# SHIELD5.net
KiCad netlist of a schematic drawn in Altium Designer
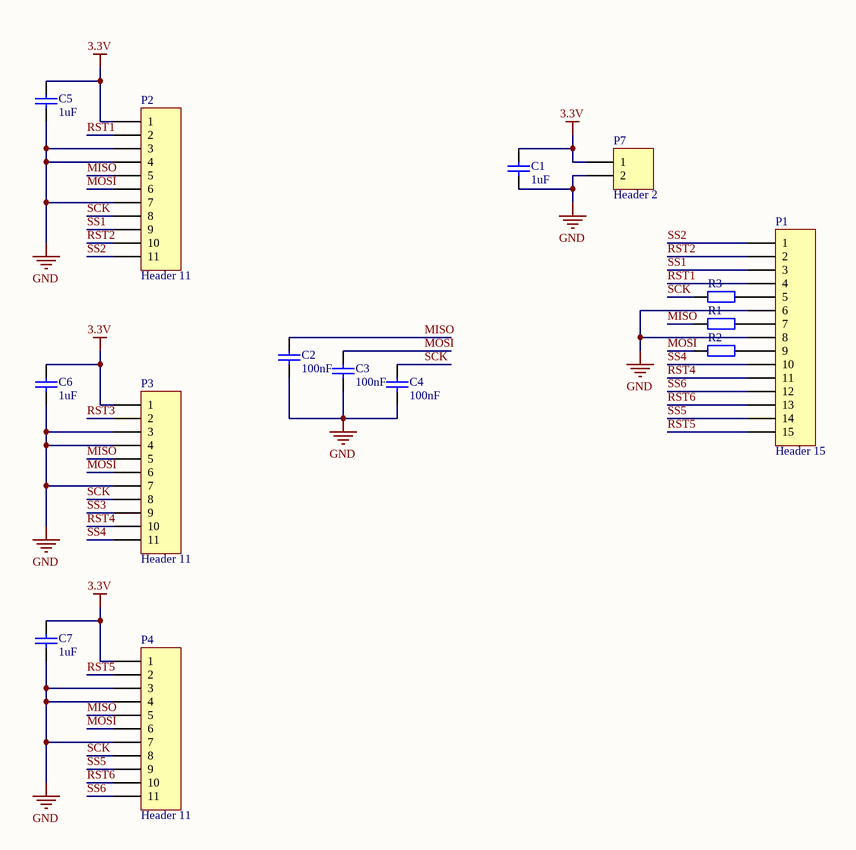
[diagram p0: SHIELD5.SchDoc]

(export (version "E")
  (design (tool "Eeschema 10.0.6"))
  (components
    (comp (ref "C1")
      (value "1uF")
      (footprint "C0805")
      (description "Capacitor")
      (fields (field (name "Comment") "Cap") (field (name "PUBLISHER") "Altium Limited"))
      (libsource (lib "Library") (part "Cap"))
    )
    (comp (ref "C2")
      (value "100nF")
      (footprint "C0805")
      (description "Capacitor")
      (fields (field (name "Comment") "Cap") (field (name "PUBLISHER") "Altium Limited"))
      (libsource (lib "Library") (part "Cap"))
    )
    (comp (ref "C3")
      (value "100nF")
      (footprint "C0805")
      (description "Capacitor")
      (fields (field (name "Comment") "Cap") (field (name "PUBLISHER") "Altium Limited"))
      (libsource (lib "Library") (part "Cap"))
    )
    (comp (ref "C4")
      (value "100nF")
      (footprint "C0805")
      (description "Capacitor")
      (fields (field (name "Comment") "Cap") (field (name "PUBLISHER") "Altium Limited"))
      (libsource (lib "Library") (part "Cap"))
    )
    (comp (ref "C5")
      (value "1uF")
      (footprint "C0805")
      (description "Capacitor")
      (fields (field (name "Comment") "Cap") (field (name "PUBLISHER") "Altium Limited"))
      (libsource (lib "Library") (part "Cap"))
    )
    (comp (ref "C6")
      (value "1uF")
      (footprint "C0805")
      (description "Capacitor")
      (fields (field (name "Comment") "Cap") (field (name "PUBLISHER") "Altium Limited"))
      (libsource (lib "Library") (part "Cap"))
    )
    (comp (ref "C7")
      (value "1uF")
      (footprint "C0805")
      (description "Capacitor")
      (fields (field (name "Comment") "Cap") (field (name "PUBLISHER") "Altium Limited"))
      (libsource (lib "Library") (part "Cap"))
    )
    (comp (ref "P1")
      (value "Header 15")
      (footprint "HDR1X15")
      (description "Header, 15-Pin")
      (fields (field (name "PUBLISHER") "Altium Limited"))
      (libsource (lib "Miscellaneous Connectors") (part "Header 15"))
    )
    (comp (ref "P2")
      (value "Header 11")
      (footprint "HDR1X11")
      (description "Header, 11-Pin")
      (fields (field (name "PUBLISHER") "Altium Limited"))
      (libsource (lib "Miscellaneous Connectors") (part "Header 11"))
    )
    (comp (ref "P3")
      (value "Header 11")
      (footprint "HDR1X11")
      (description "Header, 11-Pin")
      (fields (field (name "PUBLISHER") "Altium Limited"))
      (libsource (lib "Miscellaneous Connectors") (part "Header 11"))
    )
    (comp (ref "P4")
      (value "Header 11")
      (footprint "HDR1X11")
      (description "Header, 11-Pin")
      (fields (field (name "PUBLISHER") "Altium Limited"))
      (libsource (lib "Miscellaneous Connectors") (part "Header 11"))
    )
    (comp (ref "P7")
      (value "Header 2")
      (footprint "HDR1X2")
      (description "Header, 2-Pin")
      (fields (field (name "PUBLISHER") "Altium Limited"))
      (libsource (lib "Miscellaneous Connectors") (part "Header 2"))
    )
    (comp (ref "R1")
      (value "Res2")
      (footprint "6-0805_N")
      (description "Resistor")
      (fields (field (name "PUBLISHER") "Altium Limited"))
      (libsource (lib "Library") (part "Res2"))
    )
    (comp (ref "R2")
      (value "Res2")
      (footprint "6-0805_N")
      (description "Resistor")
      (fields (field (name "PUBLISHER") "Altium Limited"))
      (libsource (lib "Library") (part "Res2"))
    )
    (comp (ref "R3")
      (value "Res2")
      (footprint "6-0805_N")
      (description "Resistor")
      (fields (field (name "PUBLISHER") "Altium Limited"))
      (libsource (lib "Library") (part "Res2"))
    )
  )
  (nets
    (net (code "1") (name "/MISO") (class "Default")
      (node (ref "C2") (pin "2") (pinfunction "2_2") (pintype "passive"))
      (node (ref "P2") (pin "5") (pinfunction "5_5") (pintype "passive"))
      (node (ref "P3") (pin "5") (pinfunction "5_5") (pintype "passive"))
      (node (ref "P4") (pin "5") (pinfunction "5_5") (pintype "passive"))
      (node (ref "R1") (pin "1") (pinfunction "1_1") (pintype "passive"))
    )
    (net (code "2") (name "/MOSI") (class "Default")
      (node (ref "C3") (pin "1") (pinfunction "1_1") (pintype "passive"))
      (node (ref "P2") (pin "6") (pinfunction "6_6") (pintype "passive"))
      (node (ref "P3") (pin "6") (pinfunction "6_6") (pintype "passive"))
      (node (ref "P4") (pin "6") (pinfunction "6_6") (pintype "passive"))
      (node (ref "R2") (pin "1") (pinfunction "1_1") (pintype "passive"))
    )
    (net (code "3") (name "/RST1") (class "Default")
      (node (ref "P1") (pin "4") (pinfunction "4_4") (pintype "passive"))
      (node (ref "P2") (pin "2") (pinfunction "2_2") (pintype "passive"))
    )
    (net (code "4") (name "/RST2") (class "Default")
      (node (ref "P1") (pin "2") (pinfunction "2_2") (pintype "passive"))
      (node (ref "P2") (pin "10") (pinfunction "10_10") (pintype "passive"))
    )
    (net (code "5") (name "/RST3") (class "Default")
      (node (ref "P3") (pin "2") (pinfunction "2_2") (pintype "passive"))
    )
    (net (code "6") (name "/RST4") (class "Default")
      (node (ref "P1") (pin "11") (pinfunction "11_11") (pintype "passive"))
      (node (ref "P3") (pin "10") (pinfunction "10_10") (pintype "passive"))
    )
    (net (code "7") (name "/RST5") (class "Default")
      (node (ref "P1") (pin "15") (pinfunction "15_15") (pintype "passive"))
      (node (ref "P4") (pin "2") (pinfunction "2_2") (pintype "passive"))
    )
    (net (code "8") (name "/RST6") (class "Default")
      (node (ref "P1") (pin "13") (pinfunction "13_13") (pintype "passive"))
      (node (ref "P4") (pin "10") (pinfunction "10_10") (pintype "passive"))
    )
    (net (code "9") (name "/SCK") (class "Default")
      (node (ref "C4") (pin "1") (pinfunction "1_1") (pintype "passive"))
      (node (ref "P2") (pin "8") (pinfunction "8_8") (pintype "passive"))
      (node (ref "P3") (pin "8") (pinfunction "8_8") (pintype "passive"))
      (node (ref "P4") (pin "8") (pinfunction "8_8") (pintype "passive"))
      (node (ref "R3") (pin "1") (pinfunction "1_1") (pintype "passive"))
    )
    (net (code "10") (name "/SS1") (class "Default")
      (node (ref "P1") (pin "3") (pinfunction "3_3") (pintype "passive"))
      (node (ref "P2") (pin "9") (pinfunction "9_9") (pintype "passive"))
    )
    (net (code "11") (name "/SS2") (class "Default")
      (node (ref "P1") (pin "1") (pinfunction "1_1") (pintype "passive"))
      (node (ref "P2") (pin "11") (pinfunction "11_11") (pintype "passive"))
    )
    (net (code "12") (name "/SS3") (class "Default")
      (node (ref "P3") (pin "9") (pinfunction "9_9") (pintype "passive"))
    )
    (net (code "13") (name "/SS4") (class "Default")
      (node (ref "P1") (pin "10") (pinfunction "10_10") (pintype "passive"))
      (node (ref "P3") (pin "11") (pinfunction "11_11") (pintype "passive"))
    )
    (net (code "14") (name "/SS5") (class "Default")
      (node (ref "P1") (pin "14") (pinfunction "14_14") (pintype "passive"))
      (node (ref "P4") (pin "9") (pinfunction "9_9") (pintype "passive"))
    )
    (net (code "15") (name "/SS6") (class "Default")
      (node (ref "P1") (pin "12") (pinfunction "12_12") (pintype "passive"))
      (node (ref "P4") (pin "11") (pinfunction "11_11") (pintype "passive"))
    )
    (net (code "16") (name "3.3V") (class "Default")
      (node (ref "C1") (pin "2") (pinfunction "2_2") (pintype "passive"))
      (node (ref "C5") (pin "2") (pinfunction "2_2") (pintype "passive"))
      (node (ref "C6") (pin "2") (pinfunction "2_2") (pintype "passive"))
      (node (ref "C7") (pin "2") (pinfunction "2_2") (pintype "passive"))
      (node (ref "P2") (pin "1") (pinfunction "1_1") (pintype "passive"))
      (node (ref "P3") (pin "1") (pinfunction "1_1") (pintype "passive"))
      (node (ref "P4") (pin "1") (pinfunction "1_1") (pintype "passive"))
      (node (ref "P7") (pin "1") (pinfunction "1_1") (pintype "passive"))
    )
    (net (code "17") (name "GND") (class "Default")
      (node (ref "C1") (pin "1") (pinfunction "1_1") (pintype "passive"))
      (node (ref "C2") (pin "1") (pinfunction "1_1") (pintype "passive"))
      (node (ref "C3") (pin "2") (pinfunction "2_2") (pintype "passive"))
      (node (ref "C4") (pin "2") (pinfunction "2_2") (pintype "passive"))
      (node (ref "C5") (pin "1") (pinfunction "1_1") (pintype "passive"))
      (node (ref "C6") (pin "1") (pinfunction "1_1") (pintype "passive"))
      (node (ref "C7") (pin "1") (pinfunction "1_1") (pintype "passive"))
      (node (ref "P1") (pin "6") (pinfunction "6_6") (pintype "passive"))
      (node (ref "P1") (pin "8") (pinfunction "8_8") (pintype "passive"))
      (node (ref "P2") (pin "3") (pinfunction "3_3") (pintype "passive"))
      (node (ref "P2") (pin "4") (pinfunction "4_4") (pintype "passive"))
      (node (ref "P2") (pin "7") (pinfunction "7_7") (pintype "passive"))
      (node (ref "P3") (pin "3") (pinfunction "3_3") (pintype "passive"))
      (node (ref "P3") (pin "4") (pinfunction "4_4") (pintype "passive"))
      (node (ref "P3") (pin "7") (pinfunction "7_7") (pintype "passive"))
      (node (ref "P4") (pin "3") (pinfunction "3_3") (pintype "passive"))
      (node (ref "P4") (pin "4") (pinfunction "4_4") (pintype "passive"))
      (node (ref "P4") (pin "7") (pinfunction "7_7") (pintype "passive"))
      (node (ref "P7") (pin "2") (pinfunction "2_2") (pintype "passive"))
    )
    (net (code "18") (name "Net-(P1-Pad5)") (class "Default")
      (node (ref "P1") (pin "5") (pinfunction "5_5") (pintype "passive"))
      (node (ref "R3") (pin "2") (pinfunction "2_2") (pintype "passive"))
    )
    (net (code "19") (name "Net-(P1-Pad7)") (class "Default")
      (node (ref "P1") (pin "7") (pinfunction "7_7") (pintype "passive"))
      (node (ref "R1") (pin "2") (pinfunction "2_2") (pintype "passive"))
    )
    (net (code "20") (name "Net-(P1-Pad9)") (class "Default")
      (node (ref "P1") (pin "9") (pinfunction "9_9") (pintype "passive"))
      (node (ref "R2") (pin "2") (pinfunction "2_2") (pintype "passive"))
    )
  )
)
